# main.net
KiCad netlist of a schematic drawn in EAGLE
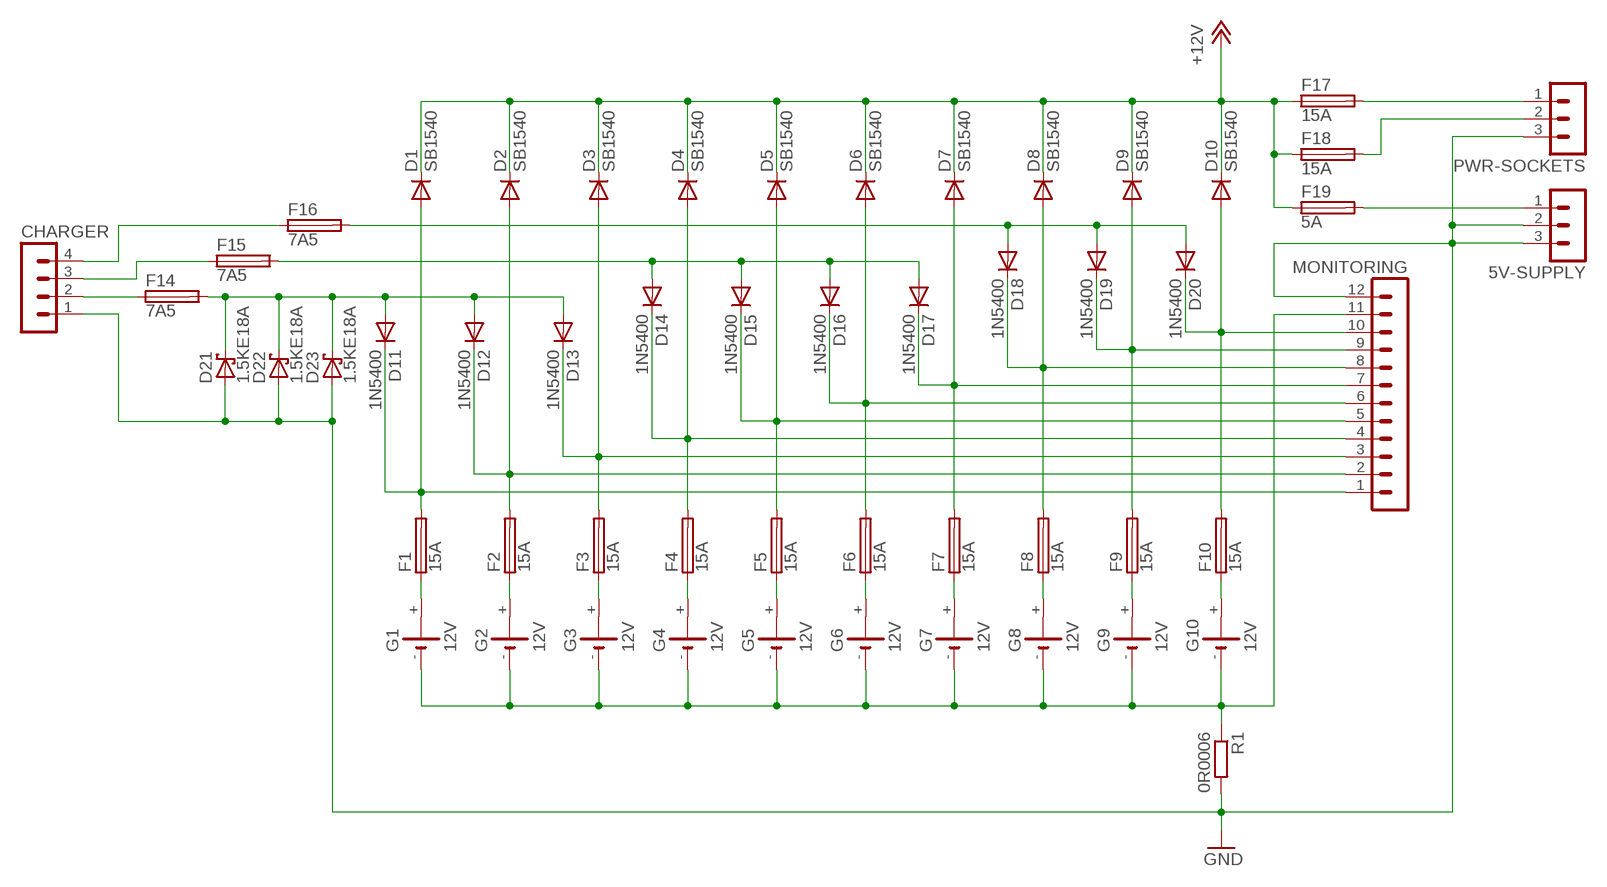
[diagram p0: schematic, sheet 1]

(export (version "E")
  (design (tool "Eeschema 10.0.6"))
  (components
    (comp (ref "5V-SUPPLY")
      (value "MA03-1")
      (footprint "eagle-import:MA03-1")
      (libsource (lib "eagle-import") (part "MA03-1"))
    )
    (comp (ref "CHARGER")
      (value "MA04-1")
      (footprint "eagle-import:MA04-1")
      (libsource (lib "eagle-import") (part "MA04-1"))
    )
    (comp (ref "D1")
      (value "SB1540")
      (footprint "eagle-import:DO41-10")
      (libsource (lib "eagle-import") (part "SB120"))
    )
    (comp (ref "D2")
      (value "SB1540")
      (footprint "eagle-import:DO41-10")
      (libsource (lib "eagle-import") (part "SB120"))
    )
    (comp (ref "D3")
      (value "SB1540")
      (footprint "eagle-import:DO41-10")
      (libsource (lib "eagle-import") (part "SB120"))
    )
    (comp (ref "D4")
      (value "SB1540")
      (footprint "eagle-import:DO41-10")
      (libsource (lib "eagle-import") (part "SB120"))
    )
    (comp (ref "D5")
      (value "SB1540")
      (footprint "eagle-import:DO41-10")
      (libsource (lib "eagle-import") (part "SB120"))
    )
    (comp (ref "D6")
      (value "SB1540")
      (footprint "eagle-import:DO41-10")
      (libsource (lib "eagle-import") (part "SB120"))
    )
    (comp (ref "D7")
      (value "SB1540")
      (footprint "eagle-import:DO41-10")
      (libsource (lib "eagle-import") (part "SB120"))
    )
    (comp (ref "D8")
      (value "SB1540")
      (footprint "eagle-import:DO41-10")
      (libsource (lib "eagle-import") (part "SB120"))
    )
    (comp (ref "D9")
      (value "SB1540")
      (footprint "eagle-import:DO41-10")
      (libsource (lib "eagle-import") (part "SB120"))
    )
    (comp (ref "D10")
      (value "SB1540")
      (footprint "eagle-import:DO41-10")
      (libsource (lib "eagle-import") (part "SB120"))
    )
    (comp (ref "D11")
      (value "1N5400")
      (footprint "eagle-import:DO201-15")
      (libsource (lib "eagle-import") (part "1N5400"))
    )
    (comp (ref "D12")
      (value "1N5400")
      (footprint "eagle-import:DO201-15")
      (libsource (lib "eagle-import") (part "1N5400"))
    )
    (comp (ref "D13")
      (value "1N5400")
      (footprint "eagle-import:DO201-15")
      (libsource (lib "eagle-import") (part "1N5400"))
    )
    (comp (ref "D14")
      (value "1N5400")
      (footprint "eagle-import:DO201-15")
      (libsource (lib "eagle-import") (part "1N5400"))
    )
    (comp (ref "D15")
      (value "1N5400")
      (footprint "eagle-import:DO201-15")
      (libsource (lib "eagle-import") (part "1N5400"))
    )
    (comp (ref "D16")
      (value "1N5400")
      (footprint "eagle-import:DO201-15")
      (libsource (lib "eagle-import") (part "1N5400"))
    )
    (comp (ref "D17")
      (value "1N5400")
      (footprint "eagle-import:DO201-15")
      (libsource (lib "eagle-import") (part "1N5400"))
    )
    (comp (ref "D18")
      (value "1N5400")
      (footprint "eagle-import:DO201-15")
      (libsource (lib "eagle-import") (part "1N5400"))
    )
    (comp (ref "D19")
      (value "1N5400")
      (footprint "eagle-import:DO201-15")
      (libsource (lib "eagle-import") (part "1N5400"))
    )
    (comp (ref "D20")
      (value "1N5400")
      (footprint "eagle-import:DO201-15")
      (libsource (lib "eagle-import") (part "1N5400"))
    )
    (comp (ref "D21")
      (value "1.5KE18A")
      (footprint "eagle-import:C1702-15")
      (libsource (lib "eagle-import") (part "P6KEXXA"))
    )
    (comp (ref "D22")
      (value "1.5KE18A")
      (footprint "eagle-import:C1702-15")
      (libsource (lib "eagle-import") (part "P6KEXXA"))
    )
    (comp (ref "D23")
      (value "1.5KE18A")
      (footprint "eagle-import:C1702-15")
      (libsource (lib "eagle-import") (part "P6KEXXA"))
    )
    (comp (ref "F1")
      (value "15A")
      (footprint "eagle-import:SH22")
      (libsource (lib "eagle-import") (part "SH22"))
    )
    (comp (ref "F2")
      (value "15A")
      (footprint "eagle-import:SH22")
      (libsource (lib "eagle-import") (part "SH22"))
    )
    (comp (ref "F3")
      (value "15A")
      (footprint "eagle-import:SH22")
      (libsource (lib "eagle-import") (part "SH22"))
    )
    (comp (ref "F4")
      (value "15A")
      (footprint "eagle-import:SH22")
      (libsource (lib "eagle-import") (part "SH22"))
    )
    (comp (ref "F5")
      (value "15A")
      (footprint "eagle-import:SH22")
      (libsource (lib "eagle-import") (part "SH22"))
    )
    (comp (ref "F6")
      (value "15A")
      (footprint "eagle-import:SH22")
      (libsource (lib "eagle-import") (part "SH22"))
    )
    (comp (ref "F7")
      (value "15A")
      (footprint "eagle-import:SH22")
      (libsource (lib "eagle-import") (part "SH22"))
    )
    (comp (ref "F8")
      (value "15A")
      (footprint "eagle-import:SH22")
      (libsource (lib "eagle-import") (part "SH22"))
    )
    (comp (ref "F9")
      (value "15A")
      (footprint "eagle-import:SH22")
      (libsource (lib "eagle-import") (part "SH22"))
    )
    (comp (ref "F10")
      (value "15A")
      (footprint "eagle-import:SH22")
      (libsource (lib "eagle-import") (part "SH22"))
    )
    (comp (ref "F14")
      (value "7A5")
      (footprint "eagle-import:SH22")
      (libsource (lib "eagle-import") (part "SH22"))
    )
    (comp (ref "F15")
      (value "7A5")
      (footprint "eagle-import:SH22")
      (libsource (lib "eagle-import") (part "SH22"))
    )
    (comp (ref "F16")
      (value "7A5")
      (footprint "eagle-import:SH22")
      (libsource (lib "eagle-import") (part "SH22"))
    )
    (comp (ref "F17")
      (value "15A")
      (footprint "eagle-import:SH22")
      (libsource (lib "eagle-import") (part "SH22"))
    )
    (comp (ref "F18")
      (value "15A")
      (footprint "eagle-import:SH22")
      (libsource (lib "eagle-import") (part "SH22"))
    )
    (comp (ref "F19")
      (value "5A")
      (footprint "eagle-import:SH22")
      (libsource (lib "eagle-import") (part "SH22"))
    )
    (comp (ref "G1")
      (value "12V")
      (footprint "eagle-import:1V60R")
      (libsource (lib "eagle-import") (part "1V60R"))
    )
    (comp (ref "G2")
      (value "12V")
      (footprint "eagle-import:1V60R")
      (libsource (lib "eagle-import") (part "1V60R"))
    )
    (comp (ref "G3")
      (value "12V")
      (footprint "eagle-import:1V60R")
      (libsource (lib "eagle-import") (part "1V60R"))
    )
    (comp (ref "G4")
      (value "12V")
      (footprint "eagle-import:1V60R")
      (libsource (lib "eagle-import") (part "1V60R"))
    )
    (comp (ref "G5")
      (value "12V")
      (footprint "eagle-import:1V60R")
      (libsource (lib "eagle-import") (part "1V60R"))
    )
    (comp (ref "G6")
      (value "12V")
      (footprint "eagle-import:1V60R")
      (libsource (lib "eagle-import") (part "1V60R"))
    )
    (comp (ref "G7")
      (value "12V")
      (footprint "eagle-import:1V60R")
      (libsource (lib "eagle-import") (part "1V60R"))
    )
    (comp (ref "G8")
      (value "12V")
      (footprint "eagle-import:1V60R")
      (libsource (lib "eagle-import") (part "1V60R"))
    )
    (comp (ref "G9")
      (value "12V")
      (footprint "eagle-import:1V60R")
      (libsource (lib "eagle-import") (part "1V60R"))
    )
    (comp (ref "G10")
      (value "12V")
      (footprint "eagle-import:1V60R")
      (libsource (lib "eagle-import") (part "1V60R"))
    )
    (comp (ref "MONITORING")
      (value "MA12-1")
      (footprint "eagle-import:MA12-1")
      (libsource (lib "eagle-import") (part "MA12-1"))
    )
    (comp (ref "PWR-SOCKETS")
      (value "MA03-1")
      (footprint "eagle-import:MA03-1")
      (libsource (lib "eagle-import") (part "MA03-1"))
    )
    (comp (ref "R1")
      (value "0R0006")
      (footprint "eagle-import:0204V")
      (libsource (lib "eagle-import") (part "R-EU_0204/2V"))
    )
  )
  (nets
    (net (code "1") (name "+12V") (class "Default")
      (node (ref "D1") (pin "C") (pinfunction "C_C") (pintype "passive"))
      (node (ref "D10") (pin "C") (pinfunction "C_C") (pintype "passive"))
      (node (ref "D2") (pin "C") (pinfunction "C_C") (pintype "passive"))
      (node (ref "D3") (pin "C") (pinfunction "C_C") (pintype "passive"))
      (node (ref "D4") (pin "C") (pinfunction "C_C") (pintype "passive"))
      (node (ref "D5") (pin "C") (pinfunction "C_C") (pintype "passive"))
      (node (ref "D6") (pin "C") (pinfunction "C_C") (pintype "passive"))
      (node (ref "D7") (pin "C") (pinfunction "C_C") (pintype "passive"))
      (node (ref "D8") (pin "C") (pinfunction "C_C") (pintype "passive"))
      (node (ref "D9") (pin "C") (pinfunction "C_C") (pintype "passive"))
      (node (ref "F17") (pin "1") (pinfunction "1_1") (pintype "passive"))
      (node (ref "F18") (pin "1") (pinfunction "1_1") (pintype "passive"))
      (node (ref "F19") (pin "1") (pinfunction "1_1") (pintype "passive"))
    )
    (net (code "2") (name "GND") (class "Default")
      (node (ref "5V-SUPPLY") (pin "2") (pinfunction "2_2") (pintype "passive"))
      (node (ref "5V-SUPPLY") (pin "3") (pinfunction "3_3") (pintype "passive"))
      (node (ref "CHARGER") (pin "1") (pinfunction "1_1") (pintype "passive"))
      (node (ref "D21") (pin "A") (pinfunction "A_A") (pintype "passive"))
      (node (ref "D22") (pin "A") (pinfunction "A_A") (pintype "passive"))
      (node (ref "D23") (pin "A") (pinfunction "A_A") (pintype "passive"))
      (node (ref "MONITORING") (pin "12") (pinfunction "12_12") (pintype "passive"))
      (node (ref "PWR-SOCKETS") (pin "3") (pinfunction "3_3") (pintype "passive"))
      (node (ref "R1") (pin "2") (pinfunction "2_2") (pintype "passive"))
    )
    (net (code "3") (name "Net-(5V-SUPPLY-Pad1)") (class "Default")
      (node (ref "5V-SUPPLY") (pin "1") (pinfunction "1_1") (pintype "passive"))
      (node (ref "F19") (pin "2") (pinfunction "2_2") (pintype "passive"))
    )
    (net (code "4") (name "Net-(CHARGER-Pad2)") (class "Default")
      (node (ref "CHARGER") (pin "2") (pinfunction "2_2") (pintype "passive"))
      (node (ref "F14") (pin "1") (pinfunction "1_1") (pintype "passive"))
    )
    (net (code "5") (name "Net-(CHARGER-Pad3)") (class "Default")
      (node (ref "CHARGER") (pin "3") (pinfunction "3_3") (pintype "passive"))
      (node (ref "F15") (pin "1") (pinfunction "1_1") (pintype "passive"))
    )
    (net (code "6") (name "Net-(CHARGER-Pad4)") (class "Default")
      (node (ref "CHARGER") (pin "4") (pinfunction "4_4") (pintype "passive"))
      (node (ref "F16") (pin "1") (pinfunction "1_1") (pintype "passive"))
    )
    (net (code "7") (name "Net-(D1-PadA)") (class "Default")
      (node (ref "D1") (pin "A") (pinfunction "A_A") (pintype "passive"))
      (node (ref "D11") (pin "C") (pinfunction "C_C") (pintype "passive"))
      (node (ref "F1") (pin "2") (pinfunction "2_2") (pintype "passive"))
      (node (ref "MONITORING") (pin "1") (pinfunction "1_1") (pintype "passive"))
    )
    (net (code "8") (name "Net-(D10-PadA)") (class "Default")
      (node (ref "D10") (pin "A") (pinfunction "A_A") (pintype "passive"))
      (node (ref "D20") (pin "C") (pinfunction "C_C") (pintype "passive"))
      (node (ref "F10") (pin "2") (pinfunction "2_2") (pintype "passive"))
      (node (ref "MONITORING") (pin "10") (pinfunction "10_10") (pintype "passive"))
    )
    (net (code "9") (name "Net-(D11-PadA)") (class "Default")
      (node (ref "D11") (pin "A") (pinfunction "A_A") (pintype "passive"))
      (node (ref "D12") (pin "A") (pinfunction "A_A") (pintype "passive"))
      (node (ref "D13") (pin "A") (pinfunction "A_A") (pintype "passive"))
      (node (ref "D21") (pin "C") (pinfunction "C_C") (pintype "passive"))
      (node (ref "D22") (pin "C") (pinfunction "C_C") (pintype "passive"))
      (node (ref "D23") (pin "C") (pinfunction "C_C") (pintype "passive"))
      (node (ref "F14") (pin "2") (pinfunction "2_2") (pintype "passive"))
    )
    (net (code "10") (name "Net-(D12-PadC)") (class "Default")
      (node (ref "D12") (pin "C") (pinfunction "C_C") (pintype "passive"))
      (node (ref "D2") (pin "A") (pinfunction "A_A") (pintype "passive"))
      (node (ref "F2") (pin "2") (pinfunction "2_2") (pintype "passive"))
      (node (ref "MONITORING") (pin "2") (pinfunction "2_2") (pintype "passive"))
    )
    (net (code "11") (name "Net-(D13-PadC)") (class "Default")
      (node (ref "D13") (pin "C") (pinfunction "C_C") (pintype "passive"))
      (node (ref "D3") (pin "A") (pinfunction "A_A") (pintype "passive"))
      (node (ref "F3") (pin "2") (pinfunction "2_2") (pintype "passive"))
      (node (ref "MONITORING") (pin "3") (pinfunction "3_3") (pintype "passive"))
    )
    (net (code "12") (name "Net-(D14-PadA)") (class "Default")
      (node (ref "D14") (pin "A") (pinfunction "A_A") (pintype "passive"))
      (node (ref "D15") (pin "A") (pinfunction "A_A") (pintype "passive"))
      (node (ref "D16") (pin "A") (pinfunction "A_A") (pintype "passive"))
      (node (ref "D17") (pin "A") (pinfunction "A_A") (pintype "passive"))
      (node (ref "F15") (pin "2") (pinfunction "2_2") (pintype "passive"))
    )
    (net (code "13") (name "Net-(D14-PadC)") (class "Default")
      (node (ref "D14") (pin "C") (pinfunction "C_C") (pintype "passive"))
      (node (ref "D4") (pin "A") (pinfunction "A_A") (pintype "passive"))
      (node (ref "F4") (pin "2") (pinfunction "2_2") (pintype "passive"))
      (node (ref "MONITORING") (pin "4") (pinfunction "4_4") (pintype "passive"))
    )
    (net (code "14") (name "Net-(D15-PadC)") (class "Default")
      (node (ref "D15") (pin "C") (pinfunction "C_C") (pintype "passive"))
      (node (ref "D5") (pin "A") (pinfunction "A_A") (pintype "passive"))
      (node (ref "F5") (pin "2") (pinfunction "2_2") (pintype "passive"))
      (node (ref "MONITORING") (pin "5") (pinfunction "5_5") (pintype "passive"))
    )
    (net (code "15") (name "Net-(D16-PadC)") (class "Default")
      (node (ref "D16") (pin "C") (pinfunction "C_C") (pintype "passive"))
      (node (ref "D6") (pin "A") (pinfunction "A_A") (pintype "passive"))
      (node (ref "F6") (pin "2") (pinfunction "2_2") (pintype "passive"))
      (node (ref "MONITORING") (pin "6") (pinfunction "6_6") (pintype "passive"))
    )
    (net (code "16") (name "Net-(D17-PadC)") (class "Default")
      (node (ref "D17") (pin "C") (pinfunction "C_C") (pintype "passive"))
      (node (ref "D7") (pin "A") (pinfunction "A_A") (pintype "passive"))
      (node (ref "F7") (pin "2") (pinfunction "2_2") (pintype "passive"))
      (node (ref "MONITORING") (pin "7") (pinfunction "7_7") (pintype "passive"))
    )
    (net (code "17") (name "Net-(D18-PadA)") (class "Default")
      (node (ref "D18") (pin "A") (pinfunction "A_A") (pintype "passive"))
      (node (ref "D19") (pin "A") (pinfunction "A_A") (pintype "passive"))
      (node (ref "D20") (pin "A") (pinfunction "A_A") (pintype "passive"))
      (node (ref "F16") (pin "2") (pinfunction "2_2") (pintype "passive"))
    )
    (net (code "18") (name "Net-(D18-PadC)") (class "Default")
      (node (ref "D18") (pin "C") (pinfunction "C_C") (pintype "passive"))
      (node (ref "D8") (pin "A") (pinfunction "A_A") (pintype "passive"))
      (node (ref "F8") (pin "2") (pinfunction "2_2") (pintype "passive"))
      (node (ref "MONITORING") (pin "8") (pinfunction "8_8") (pintype "passive"))
    )
    (net (code "19") (name "Net-(D19-PadC)") (class "Default")
      (node (ref "D19") (pin "C") (pinfunction "C_C") (pintype "passive"))
      (node (ref "D9") (pin "A") (pinfunction "A_A") (pintype "passive"))
      (node (ref "F9") (pin "2") (pinfunction "2_2") (pintype "passive"))
      (node (ref "MONITORING") (pin "9") (pinfunction "9_9") (pintype "passive"))
    )
    (net (code "20") (name "Net-(F1-Pad1)") (class "Default")
      (node (ref "F1") (pin "1") (pinfunction "1_1") (pintype "passive"))
      (node (ref "G1") (pin "+") (pinfunction "+_+") (pintype "passive"))
    )
    (net (code "21") (name "Net-(F2-Pad1)") (class "Default")
      (node (ref "F2") (pin "1") (pinfunction "1_1") (pintype "passive"))
      (node (ref "G2") (pin "+") (pinfunction "+_+") (pintype "passive"))
    )
    (net (code "22") (name "Net-(F3-Pad1)") (class "Default")
      (node (ref "F3") (pin "1") (pinfunction "1_1") (pintype "passive"))
      (node (ref "G3") (pin "+") (pinfunction "+_+") (pintype "passive"))
    )
    (net (code "23") (name "Net-(F4-Pad1)") (class "Default")
      (node (ref "F4") (pin "1") (pinfunction "1_1") (pintype "passive"))
      (node (ref "G4") (pin "+") (pinfunction "+_+") (pintype "passive"))
    )
    (net (code "24") (name "Net-(F5-Pad1)") (class "Default")
      (node (ref "F5") (pin "1") (pinfunction "1_1") (pintype "passive"))
      (node (ref "G5") (pin "+") (pinfunction "+_+") (pintype "passive"))
    )
    (net (code "25") (name "Net-(F6-Pad1)") (class "Default")
      (node (ref "F6") (pin "1") (pinfunction "1_1") (pintype "passive"))
      (node (ref "G6") (pin "+") (pinfunction "+_+") (pintype "passive"))
    )
    (net (code "26") (name "Net-(F7-Pad1)") (class "Default")
      (node (ref "F7") (pin "1") (pinfunction "1_1") (pintype "passive"))
      (node (ref "G7") (pin "+") (pinfunction "+_+") (pintype "passive"))
    )
    (net (code "27") (name "Net-(F8-Pad1)") (class "Default")
      (node (ref "F8") (pin "1") (pinfunction "1_1") (pintype "passive"))
      (node (ref "G8") (pin "+") (pinfunction "+_+") (pintype "passive"))
    )
    (net (code "28") (name "Net-(F9-Pad1)") (class "Default")
      (node (ref "F9") (pin "1") (pinfunction "1_1") (pintype "passive"))
      (node (ref "G9") (pin "+") (pinfunction "+_+") (pintype "passive"))
    )
    (net (code "29") (name "Net-(F10-Pad1)") (class "Default")
      (node (ref "F10") (pin "1") (pinfunction "1_1") (pintype "passive"))
      (node (ref "G10") (pin "+") (pinfunction "+_+") (pintype "passive"))
    )
    (net (code "30") (name "Net-(F17-Pad2)") (class "Default")
      (node (ref "F17") (pin "2") (pinfunction "2_2") (pintype "passive"))
      (node (ref "PWR-SOCKETS") (pin "1") (pinfunction "1_1") (pintype "passive"))
    )
    (net (code "31") (name "Net-(F18-Pad2)") (class "Default")
      (node (ref "F18") (pin "2") (pinfunction "2_2") (pintype "passive"))
      (node (ref "PWR-SOCKETS") (pin "2") (pinfunction "2_2") (pintype "passive"))
    )
    (net (code "32") (name "Net-(G1-Pad-)") (class "Default")
      (node (ref "G1") (pin "-") (pinfunction "-_-") (pintype "passive"))
      (node (ref "G10") (pin "-") (pinfunction "-_-") (pintype "passive"))
      (node (ref "G2") (pin "-") (pinfunction "-_-") (pintype "passive"))
      (node (ref "G3") (pin "-") (pinfunction "-_-") (pintype "passive"))
      (node (ref "G4") (pin "-") (pinfunction "-_-") (pintype "passive"))
      (node (ref "G5") (pin "-") (pinfunction "-_-") (pintype "passive"))
      (node (ref "G6") (pin "-") (pinfunction "-_-") (pintype "passive"))
      (node (ref "G7") (pin "-") (pinfunction "-_-") (pintype "passive"))
      (node (ref "G8") (pin "-") (pinfunction "-_-") (pintype "passive"))
      (node (ref "G9") (pin "-") (pinfunction "-_-") (pintype "passive"))
      (node (ref "MONITORING") (pin "11") (pinfunction "11_11") (pintype "passive"))
      (node (ref "R1") (pin "1") (pinfunction "1_1") (pintype "passive"))
    )
    (net (code "33") (name "unconnected-(G1-+-Pad+@1)") (class "Default")
      (node (ref "G1") (pin "+@1") (pinfunction "+_+@1") (pintype "passive"))
    )
    (net (code "34") (name "unconnected-(G2-+-Pad+@1)") (class "Default")
      (node (ref "G2") (pin "+@1") (pinfunction "+_+@1") (pintype "passive"))
    )
    (net (code "35") (name "unconnected-(G3-+-Pad+@1)") (class "Default")
      (node (ref "G3") (pin "+@1") (pinfunction "+_+@1") (pintype "passive"))
    )
    (net (code "36") (name "unconnected-(G4-+-Pad+@1)") (class "Default")
      (node (ref "G4") (pin "+@1") (pinfunction "+_+@1") (pintype "passive"))
    )
    (net (code "37") (name "unconnected-(G5-+-Pad+@1)") (class "Default")
      (node (ref "G5") (pin "+@1") (pinfunction "+_+@1") (pintype "passive"))
    )
    (net (code "38") (name "unconnected-(G6-+-Pad+@1)") (class "Default")
      (node (ref "G6") (pin "+@1") (pinfunction "+_+@1") (pintype "passive"))
    )
    (net (code "39") (name "unconnected-(G7-+-Pad+@1)") (class "Default")
      (node (ref "G7") (pin "+@1") (pinfunction "+_+@1") (pintype "passive"))
    )
    (net (code "40") (name "unconnected-(G8-+-Pad+@1)") (class "Default")
      (node (ref "G8") (pin "+@1") (pinfunction "+_+@1") (pintype "passive"))
    )
    (net (code "41") (name "unconnected-(G9-+-Pad+@1)") (class "Default")
      (node (ref "G9") (pin "+@1") (pinfunction "+_+@1") (pintype "passive"))
    )
    (net (code "42") (name "unconnected-(G10-+-Pad+@1)") (class "Default")
      (node (ref "G10") (pin "+@1") (pinfunction "+_+@1") (pintype "passive"))
    )
  )
)
